# Sheet_1_2023-10-06_POWERSUPPLY_SMPS.net
KiCad netlist of a schematic drawn in Altium Designer
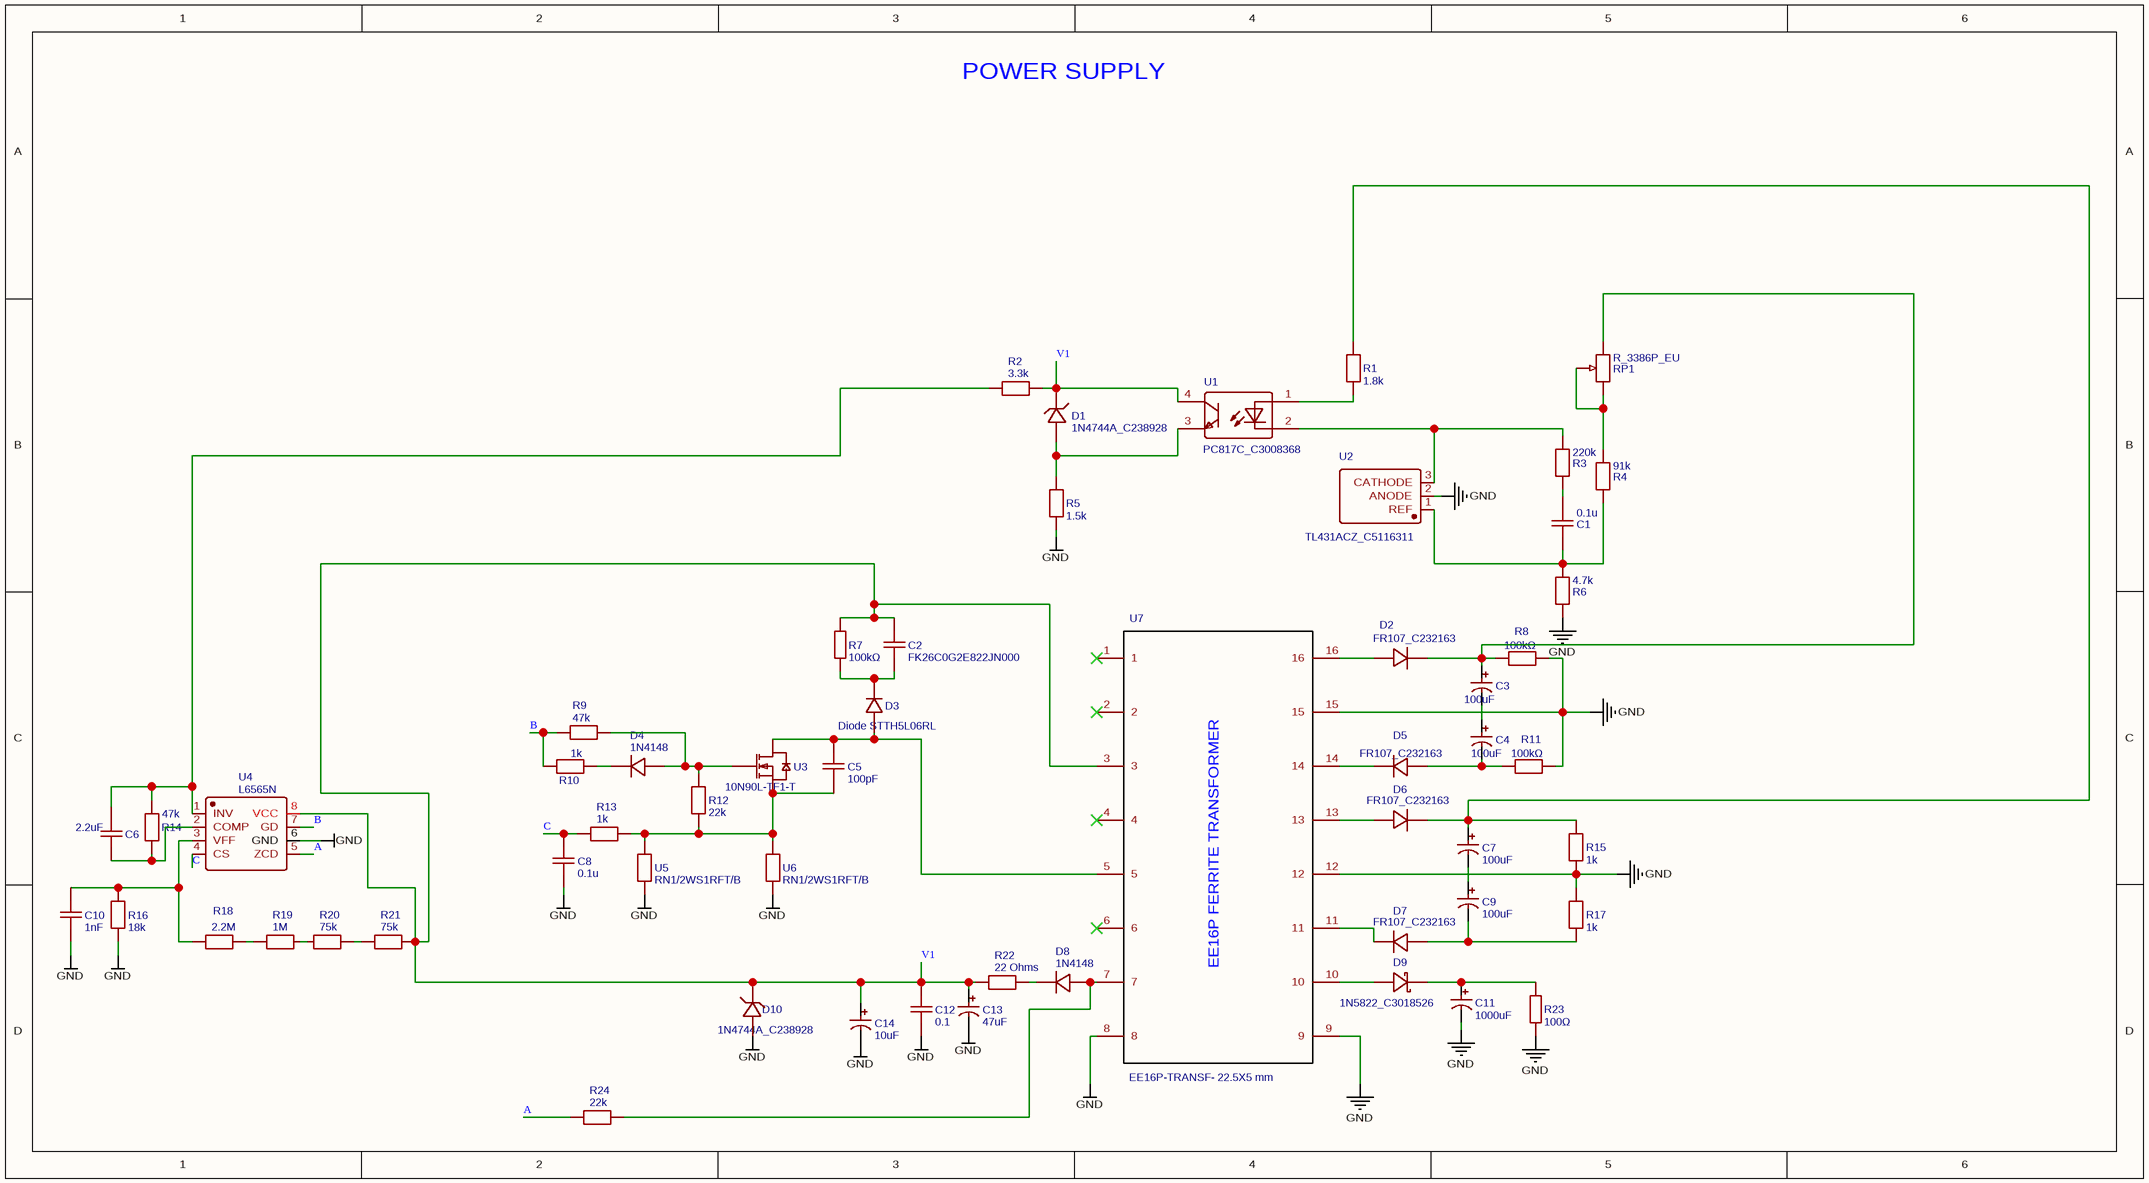
[diagram p0: Sheet_1_2023-10-06_POWERSUPPLY_SMPS.schdoc]

(export (version "E")
  (design (tool "Eeschema 10.0.6"))
  (components
    (comp (ref "C1")
      (value "0.1u")
      (fields (field (name "CONTRIBUTOR") "LCEDA_Lib"))
      (libsource (lib "altium-import") (part "root_3_0.1u_"))
    )
    (comp (ref "C2")
      (value "FK26C0G2E822JN000")
      (fields (field (name "MANUFACTURER") "TDK") (field (name "CONTRIBUTOR") "lcsc"))
      (libsource (lib "altium-import") (part "root_1_FK26C0G2E822JN000_"))
    )
    (comp (ref "C3")
      (value "100uF")
      (fields (field (name "MANUFACTURER") "AISHI(艾华集团)") (field (name "MANUFACTURER PART") "ERS1KM101G16OT"))
      (libsource (lib "altium-import") (part "root_3_100uF_"))
    )
    (comp (ref "C4")
      (value "100uF")
      (fields (field (name "MANUFACTURER") "AISHI(艾华集团)") (field (name "MANUFACTURER PART") "ERS1KM101G16OT"))
      (libsource (lib "altium-import") (part "root_3_100uF_"))
    )
    (comp (ref "C5")
      (value "100pF")
      (fields
        (field (name "MANUFACTURER") "FH(风华)")
        (field (name "MANUFACTURER PART") "CT81-N6Y5P1B101KSEW")
        (field (name "CONTRIBUTOR") "LCSC")
      )
      (libsource (lib "altium-import") (part "root_1_100pF_"))
    )
    (comp (ref "C6")
      (value "2.2uF")
      (fields (field (name "CONTRIBUTOR") "LCEDA_Lib"))
      (libsource (lib "altium-import") (part "root_3_2.2uF_"))
    )
    (comp (ref "C7")
      (value "100uF")
      (fields (field (name "MANUFACTURER") "AISHI(艾华集团)") (field (name "MANUFACTURER PART") "ERS1VM101E12OT"))
      (libsource (lib "altium-import") (part "root_3_100uF_"))
    )
    (comp (ref "C8")
      (value "0.1u")
      (fields (field (name "CONTRIBUTOR") "LCEDA_Lib"))
      (libsource (lib "altium-import") (part "root_1_0.1u_"))
    )
    (comp (ref "C9")
      (value "100uF")
      (fields (field (name "MANUFACTURER") "AISHI(艾华集团)") (field (name "MANUFACTURER PART") "ERS1VM101E12OT"))
      (libsource (lib "altium-import") (part "root_3_100uF_"))
    )
    (comp (ref "C10")
      (value "1nF")
      (fields (field (name "CONTRIBUTOR") "LCEDA_Lib"))
      (libsource (lib "altium-import") (part "root_1_1nF_"))
    )
    (comp (ref "C11")
      (value "1000uF")
      (fields
        (field (name "MANUFACTURER") "CX(承兴)")
        (field (name "MANUFACTURER PART") "KM108M016G16RR0VH2FP0")
      )
      (libsource (lib "altium-import") (part "root_3_1000uF_"))
    )
    (comp (ref "C12")
      (value "0.1")
      (fields (field (name "CONTRIBUTOR") "LCEDA_Lib"))
      (libsource (lib "altium-import") (part "root_1_0.1_"))
    )
    (comp (ref "C13")
      (value "47uF")
      (fields
        (field (name "MANUFACTURER") "rubycon(红宝石)")
        (field (name "MANUFACTURER PART") "25YXF47MEFC5X11")
      )
      (libsource (lib "altium-import") (part "root_3_47uF_"))
    )
    (comp (ref "C14")
      (value "10uF")
      (fields
        (field (name "MANUFACTURER") "CX(承兴)")
        (field (name "MANUFACTURER PART") "KM106M025D11RR0VH2FP0")
      )
      (libsource (lib "altium-import") (part "root_3_10uF_"))
    )
    (comp (ref "D1")
      (value "1N4744A_C238928")
      (fields
        (field (name "MANUFACTURER") "onsemi(安森美)")
        (field (name "MANUFACTURER PART") "1N4744A")
        (field (name "CONTRIBUTOR") "LCSC")
      )
      (libsource (lib "altium-import") (part "root_3_1N4744A_C238928_"))
    )
    (comp (ref "D2")
      (value "FR107_C232163")
      (fields
        (field (name "MANUFACTURER") "GD(固锝)")
        (field (name "MANUFACTURER PART") "FR107")
        (field (name "CONTRIBUTOR") "LCSC")
      )
      (libsource (lib "altium-import") (part "root_2_FR107_C232163_"))
    )
    (comp (ref "D3")
      (value "Diode STTH5L06RL")
      (fields
        (field (name "MANUFACTURER PART") "STMicroelectronics NV")
        (field (name "CONTRIBUTOR") "peteb2")
      )
      (libsource (lib "altium-import") (part "root_0_Diode STTH5L06RL_"))
    )
    (comp (ref "D4")
      (value "1N4148")
      (fields (field (name "MANUFACTURER") "ST(先科)"))
      (libsource (lib "altium-import") (part "root_2_1N4148_"))
    )
    (comp (ref "D5")
      (value "FR107_C232163")
      (fields
        (field (name "MANUFACTURER") "GD(固锝)")
        (field (name "MANUFACTURER PART") "FR107")
        (field (name "CONTRIBUTOR") "LCSC")
      )
      (libsource (lib "altium-import") (part "root_0_FR107_C232163_"))
    )
    (comp (ref "D6")
      (value "FR107_C232163")
      (fields
        (field (name "MANUFACTURER") "GD(固锝)")
        (field (name "MANUFACTURER PART") "FR107")
        (field (name "CONTRIBUTOR") "LCSC")
      )
      (libsource (lib "altium-import") (part "root_2_FR107_C232163_"))
    )
    (comp (ref "D7")
      (value "FR107_C232163")
      (fields
        (field (name "MANUFACTURER") "GD(固锝)")
        (field (name "MANUFACTURER PART") "FR107")
        (field (name "CONTRIBUTOR") "LCSC")
      )
      (libsource (lib "altium-import") (part "root_0_FR107_C232163_"))
    )
    (comp (ref "D8")
      (value "1N4148")
      (fields (field (name "MANUFACTURER") "ST(先科)"))
      (libsource (lib "altium-import") (part "root_2_1N4148_"))
    )
    (comp (ref "D9")
      (value "1N5822_C3018526")
      (fields
        (field (name "MANUFACTURER") "FUXINSEMI(富芯森美)")
        (field (name "MANUFACTURER PART") "1N5822")
        (field (name "CONTRIBUTOR") "lcsc")
      )
      (libsource (lib "altium-import") (part "root_2_1N5822_C3018526_"))
    )
    (comp (ref "D10")
      (value "1N4744A_C238928")
      (fields
        (field (name "MANUFACTURER") "onsemi(安森美)")
        (field (name "MANUFACTURER PART") "1N4744A")
        (field (name "CONTRIBUTOR") "LCSC")
      )
      (libsource (lib "") (part "root_3_1N4744A_C238928__1"))
    )
    (comp (ref "R1")
      (value "1.8k")
      (fields (field (name "CONTRIBUTOR") "LCEDA_Lib"))
      (libsource (lib "altium-import") (part "root_3_1.8k_"))
    )
    (comp (ref "R2")
      (value "3.3k")
      (fields (field (name "CONTRIBUTOR") "LCEDA_Lib"))
      (libsource (lib "altium-import") (part "root_2_3.3k_"))
    )
    (comp (ref "R3")
      (value "220k")
      (fields (field (name "CONTRIBUTOR") "LCEDA_Lib"))
      (libsource (lib "altium-import") (part "root_3_220k_"))
    )
    (comp (ref "R4")
      (value "91k")
      (fields (field (name "CONTRIBUTOR") "LCEDA_Lib"))
      (libsource (lib "altium-import") (part "root_3_91k_"))
    )
    (comp (ref "R5")
      (value "1.5k")
      (fields (field (name "CONTRIBUTOR") "LCEDA_Lib"))
      (libsource (lib "altium-import") (part "root_3_1.5k_"))
    )
    (comp (ref "R6")
      (value "4.7k")
      (fields (field (name "CONTRIBUTOR") "LCEDA_Lib"))
      (libsource (lib "altium-import") (part "root_3_4.7k_"))
    )
    (comp (ref "R7")
      (value "100kΩ")
      (fields
        (field (name "MANUFACTURER") "CCO(千志电子)")
        (field (name "MANUFACTURER PART") "MF1W-100KΩ±1% T")
        (field (name "CONTRIBUTOR") "LCSC")
      )
      (libsource (lib "altium-import") (part "root_1_100kΩ_"))
    )
    (comp (ref "R8")
      (value "100kΩ")
      (fields
        (field (name "MANUFACTURER") "VISHAY(威世)")
        (field (name "MANUFACTURER PART") "VR37000001003FA100")
        (field (name "CONTRIBUTOR") "lcsc")
      )
      (libsource (lib "altium-import") (part "root_0_100kΩ_"))
    )
    (comp (ref "R9")
      (value "47k")
      (fields (field (name "CONTRIBUTOR") "LCEDA_Lib"))
      (libsource (lib "altium-import") (part "root_0_47k_"))
    )
    (comp (ref "R10")
      (value "1k")
      (fields (field (name "CONTRIBUTOR") "LCEDA_Lib"))
      (libsource (lib "altium-import") (part "root_0_1k_"))
    )
    (comp (ref "R11")
      (value "100kΩ")
      (fields
        (field (name "MANUFACTURER") "VISHAY(威世)")
        (field (name "MANUFACTURER PART") "VR37000001003FA100")
        (field (name "CONTRIBUTOR") "lcsc")
      )
      (libsource (lib "altium-import") (part "root_0_100kΩ_"))
    )
    (comp (ref "R12")
      (value "22k")
      (fields (field (name "CONTRIBUTOR") "LCEDA_Lib"))
      (libsource (lib "altium-import") (part "root_1_22k_"))
    )
    (comp (ref "R13")
      (value "1k")
      (fields (field (name "CONTRIBUTOR") "LCEDA_Lib"))
      (libsource (lib "altium-import") (part "root_0_1k_"))
    )
    (comp (ref "R14")
      (value "47k")
      (fields (field (name "CONTRIBUTOR") "LCEDA_Lib"))
      (libsource (lib "altium-import") (part "root_3_47k_"))
    )
    (comp (ref "R15")
      (value "1k")
      (fields (field (name "CONTRIBUTOR") "LCEDA_Lib"))
      (libsource (lib "altium-import") (part "root_1_1k_"))
    )
    (comp (ref "R16")
      (value "18k")
      (fields (field (name "CONTRIBUTOR") "LCEDA_Lib"))
      (libsource (lib "altium-import") (part "root_1_18k_"))
    )
    (comp (ref "R17")
      (value "1k")
      (fields (field (name "CONTRIBUTOR") "LCEDA_Lib"))
      (libsource (lib "altium-import") (part "root_1_1k_"))
    )
    (comp (ref "R18")
      (value "2.2M")
      (fields (field (name "CONTRIBUTOR") "LCEDA_Lib"))
      (libsource (lib "altium-import") (part "root_0_2.2M_"))
    )
    (comp (ref "R19")
      (value "1M")
      (fields (field (name "CONTRIBUTOR") "LCEDA_Lib"))
      (libsource (lib "altium-import") (part "root_0_1M_"))
    )
    (comp (ref "R20")
      (value "75k")
      (fields (field (name "CONTRIBUTOR") "LCEDA_Lib"))
      (libsource (lib "altium-import") (part "root_0_75k_"))
    )
    (comp (ref "R21")
      (value "75k")
      (fields (field (name "CONTRIBUTOR") "LCEDA_Lib"))
      (libsource (lib "altium-import") (part "root_0_75k_"))
    )
    (comp (ref "R22")
      (value "22 Ohms")
      (fields (field (name "CONTRIBUTOR") "LCEDA_Lib"))
      (libsource (lib "altium-import") (part "root_0_22 Ohms_"))
    )
    (comp (ref "R23")
      (value "100Ω")
      (fields
        (field (name "MANUFACTURER") "VO(翔胜)")
        (field (name "MANUFACTURER PART") "KNP1WS-100Ω±5%-XT52")
        (field (name "CONTRIBUTOR") "LCSC")
      )
      (libsource (lib "altium-import") (part "root_1_100Ω_"))
    )
    (comp (ref "R24")
      (value "22k")
      (fields (field (name "CONTRIBUTOR") "LCEDA_Lib"))
      (libsource (lib "altium-import") (part "root_0_22k_"))
    )
    (comp (ref "RP1")
      (value "R_3386P_EU")
      (fields (field (name "CONTRIBUTOR") "LCEDA_Lib"))
      (libsource (lib "altium-import") (part "root_1_R_3386P_EU_"))
    )
    (comp (ref "U1")
      (value "PC817C_C3008368")
      (fields
        (field (name "MANUFACTURER") "UMW(广东友台半导体)")
        (field (name "MANUFACTURER PART") "PC817C")
        (field (name "CONTRIBUTOR") "lcsc")
      )
      (libsource (lib "altium-import") (part "root_2_PC817C_C3008368_"))
    )
    (comp (ref "U2")
      (value "TL431ACZ_C5116311")
      (fields
        (field (name "MANUFACTURER") "HGSEMI(华冠)")
        (field (name "MANUFACTURER PART") "TL431ACZ")
        (field (name "CONTRIBUTOR") "lcsc")
      )
      (libsource (lib "altium-import") (part "root_2_TL431ACZ_C5116311_"))
    )
    (comp (ref "U3")
      (value "10N90L-TF1-T")
      (fields (field (name "MANUFACTURER") "UTC(友顺)") (field (name "CONTRIBUTOR") "lcsc"))
      (libsource (lib "altium-import") (part "root_0_10N90L-TF1-T_"))
    )
    (comp (ref "U4")
      (value "L6565N")
      (fields (field (name "MANUFACTURER") "ST(意法半导体)"))
      (libsource (lib "altium-import") (part "root_0_L6565N_"))
    )
    (comp (ref "U5")
      (value "RN1/2WS1RFT/B")
      (fields (field (name "MANUFACTURER") "Tyohm(幸亚电阻)") (field (name "CONTRIBUTOR") "lcsc"))
      (libsource (lib "altium-import") (part "root_1_RN1/2WS1RFT/B_"))
    )
    (comp (ref "U6")
      (value "RN1/2WS1RFT/B")
      (fields (field (name "MANUFACTURER") "Tyohm(幸亚电阻)") (field (name "CONTRIBUTOR") "lcsc"))
      (libsource (lib "altium-import") (part "root_1_RN1/2WS1RFT/B_"))
    )
    (comp (ref "U7")
      (value "EE16P-TRANSF- 22.5X5 mm")
      (fields (field (name "CONTRIBUTOR") "venkatakrishnanr"))
      (libsource (lib "altium-import") (part "root_0_EE16P-TRANSF- 22.5X5 mm_"))
    )
  )
  (nets
    (net (code "1") (name "/A") (class "Default")
      (node (ref "R24") (pin "1") (pinfunction "1_1") (pintype "passive"))
      (node (ref "U4") (pin "5") (pinfunction "ZCD_5") (pintype "passive"))
    )
    (net (code "2") (name "/B") (class "Default")
      (node (ref "R10") (pin "1") (pinfunction "1_1") (pintype "passive"))
      (node (ref "R9") (pin "1") (pinfunction "1_1") (pintype "passive"))
      (node (ref "U4") (pin "7") (pinfunction "GD_7") (pintype "passive"))
    )
    (net (code "3") (name "/C") (class "Default")
      (node (ref "C8") (pin "2") (pinfunction "2_2") (pintype "passive"))
      (node (ref "R13") (pin "1") (pinfunction "1_1") (pintype "passive"))
      (node (ref "U4") (pin "4") (pinfunction "CS_4") (pintype "passive"))
    )
    (net (code "4") (name "/V1") (class "Default")
      (node (ref "C12") (pin "2") (pinfunction "2_2") (pintype "passive"))
      (node (ref "C13") (pin "1") (pinfunction "1_1") (pintype "passive"))
      (node (ref "C14") (pin "1") (pinfunction "1_1") (pintype "passive"))
      (node (ref "C2") (pin "2") (pinfunction "2_2") (pintype "passive"))
      (node (ref "D1") (pin "1") (pinfunction "1_1") (pintype "passive"))
      (node (ref "D10") (pin "1") (pinfunction "1_1") (pintype "passive"))
      (node (ref "R2") (pin "1") (pinfunction "1_1") (pintype "passive"))
      (node (ref "R21") (pin "2") (pinfunction "2_2") (pintype "passive"))
      (node (ref "R22") (pin "1") (pinfunction "1_1") (pintype "passive"))
      (node (ref "R7") (pin "2") (pinfunction "2_2") (pintype "passive"))
      (node (ref "U1") (pin "4") (pinfunction "COL_4") (pintype "passive"))
      (node (ref "U4") (pin "8") (pinfunction "VCC_8") (pintype "passive"))
      (node (ref "U7") (pin "3") (pinfunction "3_3") (pintype "passive"))
    )
    (net (code "5") (name "GND") (class "Default")
      (node (ref "C10") (pin "1") (pinfunction "1_1") (pintype "passive"))
      (node (ref "C11") (pin "2") (pinfunction "2_2") (pintype "passive"))
      (node (ref "C12") (pin "1") (pinfunction "1_1") (pintype "passive"))
      (node (ref "C13") (pin "2") (pinfunction "2_2") (pintype "passive"))
      (node (ref "C14") (pin "2") (pinfunction "2_2") (pintype "passive"))
      (node (ref "C8") (pin "1") (pinfunction "1_1") (pintype "passive"))
      (node (ref "D10") (pin "2") (pinfunction "2_2") (pintype "passive"))
      (node (ref "R11") (pin "2") (pinfunction "2_2") (pintype "passive"))
      (node (ref "R15") (pin "1") (pinfunction "1_1") (pintype "passive"))
      (node (ref "R16") (pin "1") (pinfunction "1_1") (pintype "passive"))
      (node (ref "R17") (pin "2") (pinfunction "2_2") (pintype "passive"))
      (node (ref "R23") (pin "1") (pinfunction "1_1") (pintype "passive"))
      (node (ref "R5") (pin "2") (pinfunction "2_2") (pintype "passive"))
      (node (ref "R6") (pin "1") (pinfunction "1_1") (pintype "passive"))
      (node (ref "R8") (pin "2") (pinfunction "2_2") (pintype "passive"))
      (node (ref "U2") (pin "2") (pinfunction "ANODE_2") (pintype "passive"))
      (node (ref "U4") (pin "6") (pinfunction "GND_6") (pintype "passive"))
      (node (ref "U5") (pin "1") (pinfunction "1_1") (pintype "passive"))
      (node (ref "U6") (pin "1") (pinfunction "1_1") (pintype "passive"))
      (node (ref "U7") (pin "12") (pinfunction "12_12") (pintype "passive"))
      (node (ref "U7") (pin "15") (pinfunction "15_15") (pintype "passive"))
      (node (ref "U7") (pin "8") (pinfunction "8_8") (pintype "passive"))
      (node (ref "U7") (pin "9") (pinfunction "9_9") (pintype "passive"))
    )
    (net (code "6") (name "Net-(C1-Pad2)") (class "Default")
      (node (ref "C1") (pin "2") (pinfunction "2_2") (pintype "passive"))
      (node (ref "R3") (pin "1") (pinfunction "1_1") (pintype "passive"))
    )
    (net (code "7") (name "Net-(C3-Pad2)") (class "Default")
      (node (ref "C3") (pin "2") (pinfunction "2_2") (pintype "passive"))
      (node (ref "C4") (pin "1") (pinfunction "1_1") (pintype "passive"))
    )
    (net (code "8") (name "Net-(C7-Pad2)") (class "Default")
      (node (ref "C7") (pin "2") (pinfunction "2_2") (pintype "passive"))
      (node (ref "C9") (pin "1") (pinfunction "1_1") (pintype "passive"))
    )
    (net (code "9") (name "Net-(D2-A)") (class "Default")
      (node (ref "D2") (pin "2") (pinfunction "A_2") (pintype "passive"))
      (node (ref "U7") (pin "16") (pinfunction "16_16") (pintype "passive"))
    )
    (net (code "10") (name "Net-(D2-C)") (class "Default")
      (node (ref "C3") (pin "1") (pinfunction "1_1") (pintype "passive"))
      (node (ref "D2") (pin "1") (pinfunction "C_1") (pintype "passive"))
      (node (ref "R8") (pin "1") (pinfunction "1_1") (pintype "passive"))
      (node (ref "RP1") (pin "1") (pinfunction "1_1") (pintype "passive"))
    )
    (net (code "11") (name "Net-(D3-A)") (class "Default")
      (node (ref "C5") (pin "2") (pinfunction "2_2") (pintype "passive"))
      (node (ref "D3") (pin "1") (pinfunction "A_1") (pintype "passive"))
      (node (ref "U3") (pin "2") (pinfunction "D_2") (pintype "passive"))
      (node (ref "U7") (pin "5") (pinfunction "5_5") (pintype "passive"))
    )
    (net (code "12") (name "Net-(D3-K)") (class "Default")
      (node (ref "C2") (pin "1") (pinfunction "1_1") (pintype "passive"))
      (node (ref "D3") (pin "2") (pinfunction "K_2") (pintype "passive"))
      (node (ref "R7") (pin "1") (pinfunction "1_1") (pintype "passive"))
    )
    (net (code "13") (name "Net-(D4-A)") (class "Default")
      (node (ref "D4") (pin "1") (pinfunction "A_1") (pintype "passive"))
      (node (ref "R12") (pin "2") (pinfunction "2_2") (pintype "passive"))
      (node (ref "R9") (pin "2") (pinfunction "2_2") (pintype "passive"))
      (node (ref "U3") (pin "1") (pinfunction "G_1") (pintype "passive"))
    )
    (net (code "14") (name "Net-(D4-C)") (class "Default")
      (node (ref "D4") (pin "2") (pinfunction "C_2") (pintype "passive"))
      (node (ref "R10") (pin "2") (pinfunction "2_2") (pintype "passive"))
    )
    (net (code "15") (name "Net-(D5-A)") (class "Default")
      (node (ref "C4") (pin "2") (pinfunction "2_2") (pintype "passive"))
      (node (ref "D5") (pin "2") (pinfunction "A_2") (pintype "passive"))
      (node (ref "R11") (pin "1") (pinfunction "1_1") (pintype "passive"))
    )
    (net (code "16") (name "Net-(D5-C)") (class "Default")
      (node (ref "D5") (pin "1") (pinfunction "C_1") (pintype "passive"))
      (node (ref "U7") (pin "14") (pinfunction "14_14") (pintype "passive"))
    )
    (net (code "17") (name "Net-(D6-A)") (class "Default")
      (node (ref "D6") (pin "2") (pinfunction "A_2") (pintype "passive"))
      (node (ref "U7") (pin "13") (pinfunction "13_13") (pintype "passive"))
    )
    (net (code "18") (name "Net-(D6-C)") (class "Default")
      (node (ref "C7") (pin "1") (pinfunction "1_1") (pintype "passive"))
      (node (ref "D6") (pin "1") (pinfunction "C_1") (pintype "passive"))
      (node (ref "R1") (pin "1") (pinfunction "1_1") (pintype "passive"))
      (node (ref "R15") (pin "2") (pinfunction "2_2") (pintype "passive"))
    )
    (net (code "19") (name "Net-(D7-A)") (class "Default")
      (node (ref "C9") (pin "2") (pinfunction "2_2") (pintype "passive"))
      (node (ref "D7") (pin "2") (pinfunction "A_2") (pintype "passive"))
      (node (ref "R17") (pin "1") (pinfunction "1_1") (pintype "passive"))
    )
    (net (code "20") (name "Net-(D7-C)") (class "Default")
      (node (ref "D7") (pin "1") (pinfunction "C_1") (pintype "passive"))
      (node (ref "U7") (pin "11") (pinfunction "11_11") (pintype "passive"))
    )
    (net (code "21") (name "Net-(D8-A)") (class "Default")
      (node (ref "D8") (pin "1") (pinfunction "A_1") (pintype "passive"))
      (node (ref "R24") (pin "2") (pinfunction "2_2") (pintype "passive"))
      (node (ref "U7") (pin "7") (pinfunction "7_7") (pintype "passive"))
    )
    (net (code "22") (name "Net-(D8-C)") (class "Default")
      (node (ref "D8") (pin "2") (pinfunction "C_2") (pintype "passive"))
      (node (ref "R22") (pin "2") (pinfunction "2_2") (pintype "passive"))
    )
    (net (code "23") (name "Net-(D9-A)") (class "Default")
      (node (ref "D9") (pin "1") (pinfunction "A_1") (pintype "passive"))
      (node (ref "U7") (pin "10") (pinfunction "10_10") (pintype "passive"))
    )
    (net (code "24") (name "Net-(D9-K)") (class "Default")
      (node (ref "C11") (pin "1") (pinfunction "1_1") (pintype "passive"))
      (node (ref "D9") (pin "2") (pinfunction "K_2") (pintype "passive"))
      (node (ref "R23") (pin "2") (pinfunction "2_2") (pintype "passive"))
    )
    (net (code "25") (name "Net-(R4-Pad2)") (class "Default")
      (node (ref "R4") (pin "2") (pinfunction "2_2") (pintype "passive"))
      (node (ref "RP1") (pin "2") (pinfunction "2_2") (pintype "passive"))
      (node (ref "RP1") (pin "3") (pinfunction "3_3") (pintype "passive"))
    )
    (net (code "26") (name "Net-(R18-Pad2)") (class "Default")
      (node (ref "R18") (pin "2") (pinfunction "2_2") (pintype "passive"))
      (node (ref "R19") (pin "1") (pinfunction "1_1") (pintype "passive"))
    )
    (net (code "27") (name "Net-(R19-Pad2)") (class "Default")
      (node (ref "R19") (pin "2") (pinfunction "2_2") (pintype "passive"))
      (node (ref "R20") (pin "1") (pinfunction "1_1") (pintype "passive"))
    )
    (net (code "28") (name "Net-(R20-Pad2)") (class "Default")
      (node (ref "R20") (pin "2") (pinfunction "2_2") (pintype "passive"))
      (node (ref "R21") (pin "1") (pinfunction "1_1") (pintype "passive"))
    )
    (net (code "29") (name "Net-(U1-AN)") (class "Default")
      (node (ref "R1") (pin "2") (pinfunction "2_2") (pintype "passive"))
      (node (ref "U1") (pin "1") (pinfunction "AN_1") (pintype "passive"))
    )
    (net (code "30") (name "Net-(U1-CAT)") (class "Default")
      (node (ref "R3") (pin "2") (pinfunction "2_2") (pintype "passive"))
      (node (ref "U1") (pin "2") (pinfunction "CAT_2") (pintype "passive"))
      (node (ref "U2") (pin "3") (pinfunction "CATHODE_3") (pintype "passive"))
    )
    (net (code "31") (name "Net-(U1-EM)") (class "Default")
      (node (ref "D1") (pin "2") (pinfunction "2_2") (pintype "passive"))
      (node (ref "R5") (pin "1") (pinfunction "1_1") (pintype "passive"))
      (node (ref "U1") (pin "3") (pinfunction "EM_3") (pintype "passive"))
    )
    (net (code "32") (name "Net-(U2-REF)") (class "Default")
      (node (ref "C1") (pin "1") (pinfunction "1_1") (pintype "passive"))
      (node (ref "R4") (pin "1") (pinfunction "1_1") (pintype "passive"))
      (node (ref "R6") (pin "2") (pinfunction "2_2") (pintype "passive"))
      (node (ref "U2") (pin "1") (pinfunction "REF_1") (pintype "passive"))
    )
    (net (code "33") (name "Net-(U3-S)") (class "Default")
      (node (ref "C5") (pin "1") (pinfunction "1_1") (pintype "passive"))
      (node (ref "R12") (pin "1") (pinfunction "1_1") (pintype "passive"))
      (node (ref "R13") (pin "2") (pinfunction "2_2") (pintype "passive"))
      (node (ref "U3") (pin "3") (pinfunction "S_3") (pintype "passive"))
      (node (ref "U5") (pin "2") (pinfunction "2_2") (pintype "passive"))
      (node (ref "U6") (pin "2") (pinfunction "2_2") (pintype "passive"))
    )
    (net (code "34") (name "Net-(U4-COMP)") (class "Default")
      (node (ref "C6") (pin "2") (pinfunction "2_2") (pintype "passive"))
      (node (ref "R14") (pin "2") (pinfunction "2_2") (pintype "passive"))
      (node (ref "U4") (pin "2") (pinfunction "COMP_2") (pintype "passive"))
    )
    (net (code "35") (name "Net-(U4-INV)") (class "Default")
      (node (ref "C6") (pin "1") (pinfunction "1_1") (pintype "passive"))
      (node (ref "R14") (pin "1") (pinfunction "1_1") (pintype "passive"))
      (node (ref "R2") (pin "2") (pinfunction "2_2") (pintype "passive"))
      (node (ref "U4") (pin "1") (pinfunction "INV_1") (pintype "passive"))
    )
    (net (code "36") (name "Net-(U4-VFF)") (class "Default")
      (node (ref "C10") (pin "2") (pinfunction "2_2") (pintype "passive"))
      (node (ref "R16") (pin "2") (pinfunction "2_2") (pintype "passive"))
      (node (ref "R18") (pin "1") (pinfunction "1_1") (pintype "passive"))
      (node (ref "U4") (pin "3") (pinfunction "VFF_3") (pintype "passive"))
    )
    (net (code "37") (name "unconnected-(U7-Pad1)") (class "Default")
      (node (ref "U7") (pin "1") (pinfunction "1_1") (pintype "passive+no_connect"))
    )
    (net (code "38") (name "unconnected-(U7-Pad2)") (class "Default")
      (node (ref "U7") (pin "2") (pinfunction "2_2") (pintype "passive+no_connect"))
    )
    (net (code "39") (name "unconnected-(U7-Pad4)") (class "Default")
      (node (ref "U7") (pin "4") (pinfunction "4_4") (pintype "passive+no_connect"))
    )
    (net (code "40") (name "unconnected-(U7-Pad6)") (class "Default")
      (node (ref "U7") (pin "6") (pinfunction "6_6") (pintype "passive+no_connect"))
    )
  )
)
